# CON_NB3000_LEDKB.net
KiCad netlist of a schematic drawn in Altium Designer
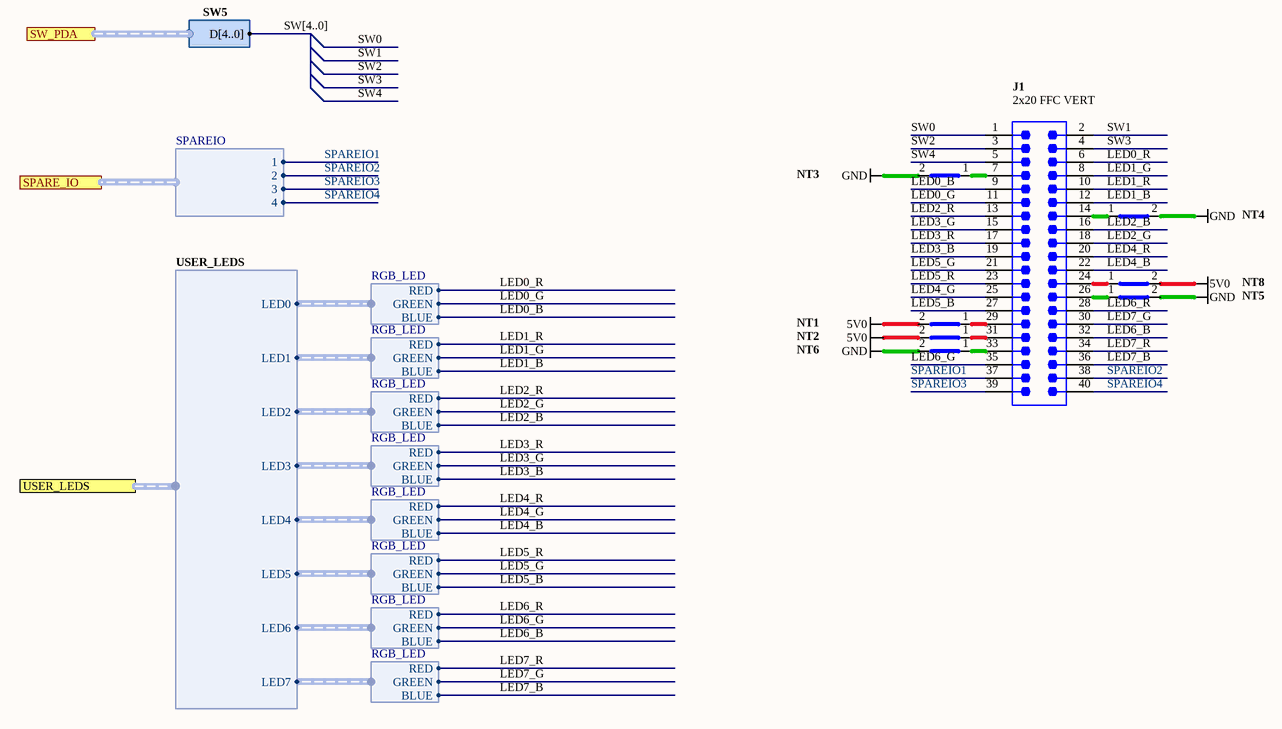
[diagram p0: CON_NB3000_LEDKB.SCHDOC]

(export (version "E")
  (design (tool "Eeschema 10.0.6"))
  (components
    (comp (ref "J1")
      (value "2x20 FFC VERT")
      (footprint "FPC-xxS1VN3R")
      (description "Header FFC, 2x20 pin Vertical, 0.5mm")
      (libsource (lib "AltiumDesignLibrary") (part "CON-FFC-2x20-VERT"))
    )
    (comp (ref "NT1")
      (value "Net Tie SMT2")
      (footprint "NETTIE-SMT2-8X8")
      (description "Net-Tie, Surface Mount, 2 x 1.6mm x 0.8mm SMT Pads - For 0.8mm Track")
      (libsource (lib "AltiumDesignLibrary") (part "NETTIE-SMT2"))
    )
    (comp (ref "NT2")
      (value "Net Tie SMT2")
      (footprint "NETTIE-SMT2-8X8")
      (description "Net-Tie, Surface Mount, 2 x 1.6mm x 0.8mm SMT Pads - For 0.8mm Track")
      (libsource (lib "AltiumDesignLibrary") (part "NETTIE-SMT2"))
    )
    (comp (ref "NT3")
      (value "Net Tie SMT2")
      (footprint "NETTIE-SMT2-8X8")
      (description "Net-Tie, Surface Mount, 2 x 1.6mm x 0.8mm SMT Pads - For 0.8mm Track")
      (libsource (lib "AltiumDesignLibrary") (part "NETTIE-SMT2"))
    )
    (comp (ref "NT4")
      (value "Net Tie SMT2")
      (footprint "NETTIE-SMT2-8X8")
      (description "Net-Tie, Surface Mount, 2 x 1.6mm x 0.8mm SMT Pads - For 0.8mm Track")
      (libsource (lib "AltiumDesignLibrary") (part "NETTIE-SMT2"))
    )
    (comp (ref "NT5")
      (value "Net Tie SMT2")
      (footprint "NETTIE-SMT2-8X8")
      (description "Net-Tie, Surface Mount, 2 x 1.6mm x 0.8mm SMT Pads - For 0.8mm Track")
      (libsource (lib "AltiumDesignLibrary") (part "NETTIE-SMT2"))
    )
    (comp (ref "NT6")
      (value "Net Tie SMT2")
      (footprint "NETTIE-SMT2-8X8")
      (description "Net-Tie, Surface Mount, 2 x 1.6mm x 0.8mm SMT Pads - For 0.8mm Track")
      (libsource (lib "AltiumDesignLibrary") (part "NETTIE-SMT2"))
    )
    (comp (ref "NT8")
      (value "Net Tie SMT2")
      (footprint "NETTIE-SMT2-8X8")
      (description "Net-Tie, Surface Mount, 2 x 1.6mm x 0.8mm SMT Pads - For 0.8mm Track")
      (libsource (lib "AltiumDesignLibrary") (part "NETTIE-SMT2"))
    )
  )
  (nets
    (net (code "6") (name "/LED0_B") (class "Default")
      (node (ref "J1") (pin "9") (pinfunction "9_9") (pintype "passive"))
    )
    (net (code "7") (name "/LED0_G") (class "Default")
      (node (ref "J1") (pin "11") (pinfunction "11_11") (pintype "passive"))
    )
    (net (code "8") (name "/LED0_R") (class "Default")
      (node (ref "J1") (pin "6") (pinfunction "6_6") (pintype "passive"))
    )
    (net (code "9") (name "/LED1_B") (class "Default")
      (node (ref "J1") (pin "12") (pinfunction "12_12") (pintype "passive"))
    )
    (net (code "10") (name "/LED1_G") (class "Default")
      (node (ref "J1") (pin "8") (pinfunction "8_8") (pintype "passive"))
    )
    (net (code "11") (name "/LED1_R") (class "Default")
      (node (ref "J1") (pin "10") (pinfunction "10_10") (pintype "passive"))
    )
    (net (code "12") (name "/LED2_B") (class "Default")
      (node (ref "J1") (pin "16") (pinfunction "16_16") (pintype "passive"))
    )
    (net (code "13") (name "/LED2_G") (class "Default")
      (node (ref "J1") (pin "18") (pinfunction "18_18") (pintype "passive"))
    )
    (net (code "14") (name "/LED2_R") (class "Default")
      (node (ref "J1") (pin "13") (pinfunction "13_13") (pintype "passive"))
    )
    (net (code "15") (name "/LED3_B") (class "Default")
      (node (ref "J1") (pin "19") (pinfunction "19_19") (pintype "passive"))
    )
    (net (code "16") (name "/LED3_G") (class "Default")
      (node (ref "J1") (pin "15") (pinfunction "15_15") (pintype "passive"))
    )
    (net (code "17") (name "/LED3_R") (class "Default")
      (node (ref "J1") (pin "17") (pinfunction "17_17") (pintype "passive"))
    )
    (net (code "18") (name "/LED4_B") (class "Default")
      (node (ref "J1") (pin "22") (pinfunction "22_22") (pintype "passive"))
    )
    (net (code "19") (name "/LED4_G") (class "Default")
      (node (ref "J1") (pin "25") (pinfunction "25_25") (pintype "passive"))
    )
    (net (code "20") (name "/LED4_R") (class "Default")
      (node (ref "J1") (pin "20") (pinfunction "20_20") (pintype "passive"))
    )
    (net (code "21") (name "/LED5_B") (class "Default")
      (node (ref "J1") (pin "27") (pinfunction "27_27") (pintype "passive"))
    )
    (net (code "22") (name "/LED5_G") (class "Default")
      (node (ref "J1") (pin "21") (pinfunction "21_21") (pintype "passive"))
    )
    (net (code "23") (name "/LED5_R") (class "Default")
      (node (ref "J1") (pin "23") (pinfunction "23_23") (pintype "passive"))
    )
    (net (code "24") (name "/LED6_B") (class "Default")
      (node (ref "J1") (pin "32") (pinfunction "32_32") (pintype "passive"))
    )
    (net (code "25") (name "/LED6_G") (class "Default")
      (node (ref "J1") (pin "35") (pinfunction "35_35") (pintype "passive"))
    )
    (net (code "26") (name "/LED6_R") (class "Default")
      (node (ref "J1") (pin "28") (pinfunction "28_28") (pintype "passive"))
    )
    (net (code "27") (name "/LED7_B") (class "Default")
      (node (ref "J1") (pin "36") (pinfunction "36_36") (pintype "passive"))
    )
    (net (code "28") (name "/LED7_G") (class "Default")
      (node (ref "J1") (pin "30") (pinfunction "30_30") (pintype "passive"))
    )
    (net (code "29") (name "/LED7_R") (class "Default")
      (node (ref "J1") (pin "34") (pinfunction "34_34") (pintype "passive"))
    )
    (net (code "30") (name "/SPAREIO1") (class "Default")
      (node (ref "J1") (pin "37") (pinfunction "37_37") (pintype "passive"))
    )
    (net (code "31") (name "/SPAREIO2") (class "Default")
      (node (ref "J1") (pin "38") (pinfunction "38_38") (pintype "passive"))
    )
    (net (code "32") (name "/SPAREIO3") (class "Default")
      (node (ref "J1") (pin "39") (pinfunction "39_39") (pintype "passive"))
    )
    (net (code "33") (name "/SPAREIO4") (class "Default")
      (node (ref "J1") (pin "40") (pinfunction "40_40") (pintype "passive"))
    )
    (net (code "34") (name "/SW0") (class "Default")
      (node (ref "J1") (pin "1") (pinfunction "1_1") (pintype "passive"))
    )
    (net (code "35") (name "/SW1") (class "Default")
      (node (ref "J1") (pin "2") (pinfunction "2_2") (pintype "passive"))
    )
    (net (code "36") (name "/SW2") (class "Default")
      (node (ref "J1") (pin "3") (pinfunction "3_3") (pintype "passive"))
    )
    (net (code "37") (name "/SW3") (class "Default")
      (node (ref "J1") (pin "4") (pinfunction "4_4") (pintype "passive"))
    )
    (net (code "38") (name "/SW4") (class "Default")
      (node (ref "J1") (pin "5") (pinfunction "5_5") (pintype "passive"))
    )
    (net (code "45") (name "5V0") (class "Default")
      (node (ref "NT1") (pin "2") (pinfunction "Net2_2") (pintype "passive"))
      (node (ref "NT2") (pin "2") (pinfunction "Net2_2") (pintype "passive"))
      (node (ref "NT8") (pin "2") (pinfunction "Net2_2") (pintype "passive"))
    )
    (net (code "46") (name "GND") (class "Default")
      (node (ref "NT3") (pin "2") (pinfunction "Net2_2") (pintype "passive"))
      (node (ref "NT4") (pin "2") (pinfunction "Net2_2") (pintype "passive"))
      (node (ref "NT5") (pin "2") (pinfunction "Net2_2") (pintype "passive"))
      (node (ref "NT6") (pin "2") (pinfunction "Net2_2") (pintype "passive"))
    )
    (net (code "47") (name "Net-(NT1-Net1)") (class "Default")
      (node (ref "J1") (pin "29") (pinfunction "29_29") (pintype "passive"))
      (node (ref "NT1") (pin "1") (pinfunction "Net1_1") (pintype "passive"))
    )
    (net (code "48") (name "Net-(NT2-Net1)") (class "Default")
      (node (ref "J1") (pin "31") (pinfunction "31_31") (pintype "passive"))
      (node (ref "NT2") (pin "1") (pinfunction "Net1_1") (pintype "passive"))
    )
    (net (code "49") (name "Net-(NT3-Net1)") (class "Default")
      (node (ref "J1") (pin "7") (pinfunction "7_7") (pintype "passive"))
      (node (ref "NT3") (pin "1") (pinfunction "Net1_1") (pintype "passive"))
    )
    (net (code "50") (name "Net-(NT4-Net1)") (class "Default")
      (node (ref "J1") (pin "14") (pinfunction "14_14") (pintype "passive"))
      (node (ref "NT4") (pin "1") (pinfunction "Net1_1") (pintype "passive"))
    )
    (net (code "51") (name "Net-(NT5-Net1)") (class "Default")
      (node (ref "J1") (pin "26") (pinfunction "26_26") (pintype "passive"))
      (node (ref "NT5") (pin "1") (pinfunction "Net1_1") (pintype "passive"))
    )
    (net (code "52") (name "Net-(NT6-Net1)") (class "Default")
      (node (ref "J1") (pin "33") (pinfunction "33_33") (pintype "passive"))
      (node (ref "NT6") (pin "1") (pinfunction "Net1_1") (pintype "passive"))
    )
    (net (code "53") (name "Net-(NT8-Net1)") (class "Default")
      (node (ref "J1") (pin "24") (pinfunction "24_24") (pintype "passive"))
      (node (ref "NT8") (pin "1") (pinfunction "Net1_1") (pintype "passive"))
    )
  )
)
